# gizmo.net
KiCad netlist of a schematic drawn in EAGLE
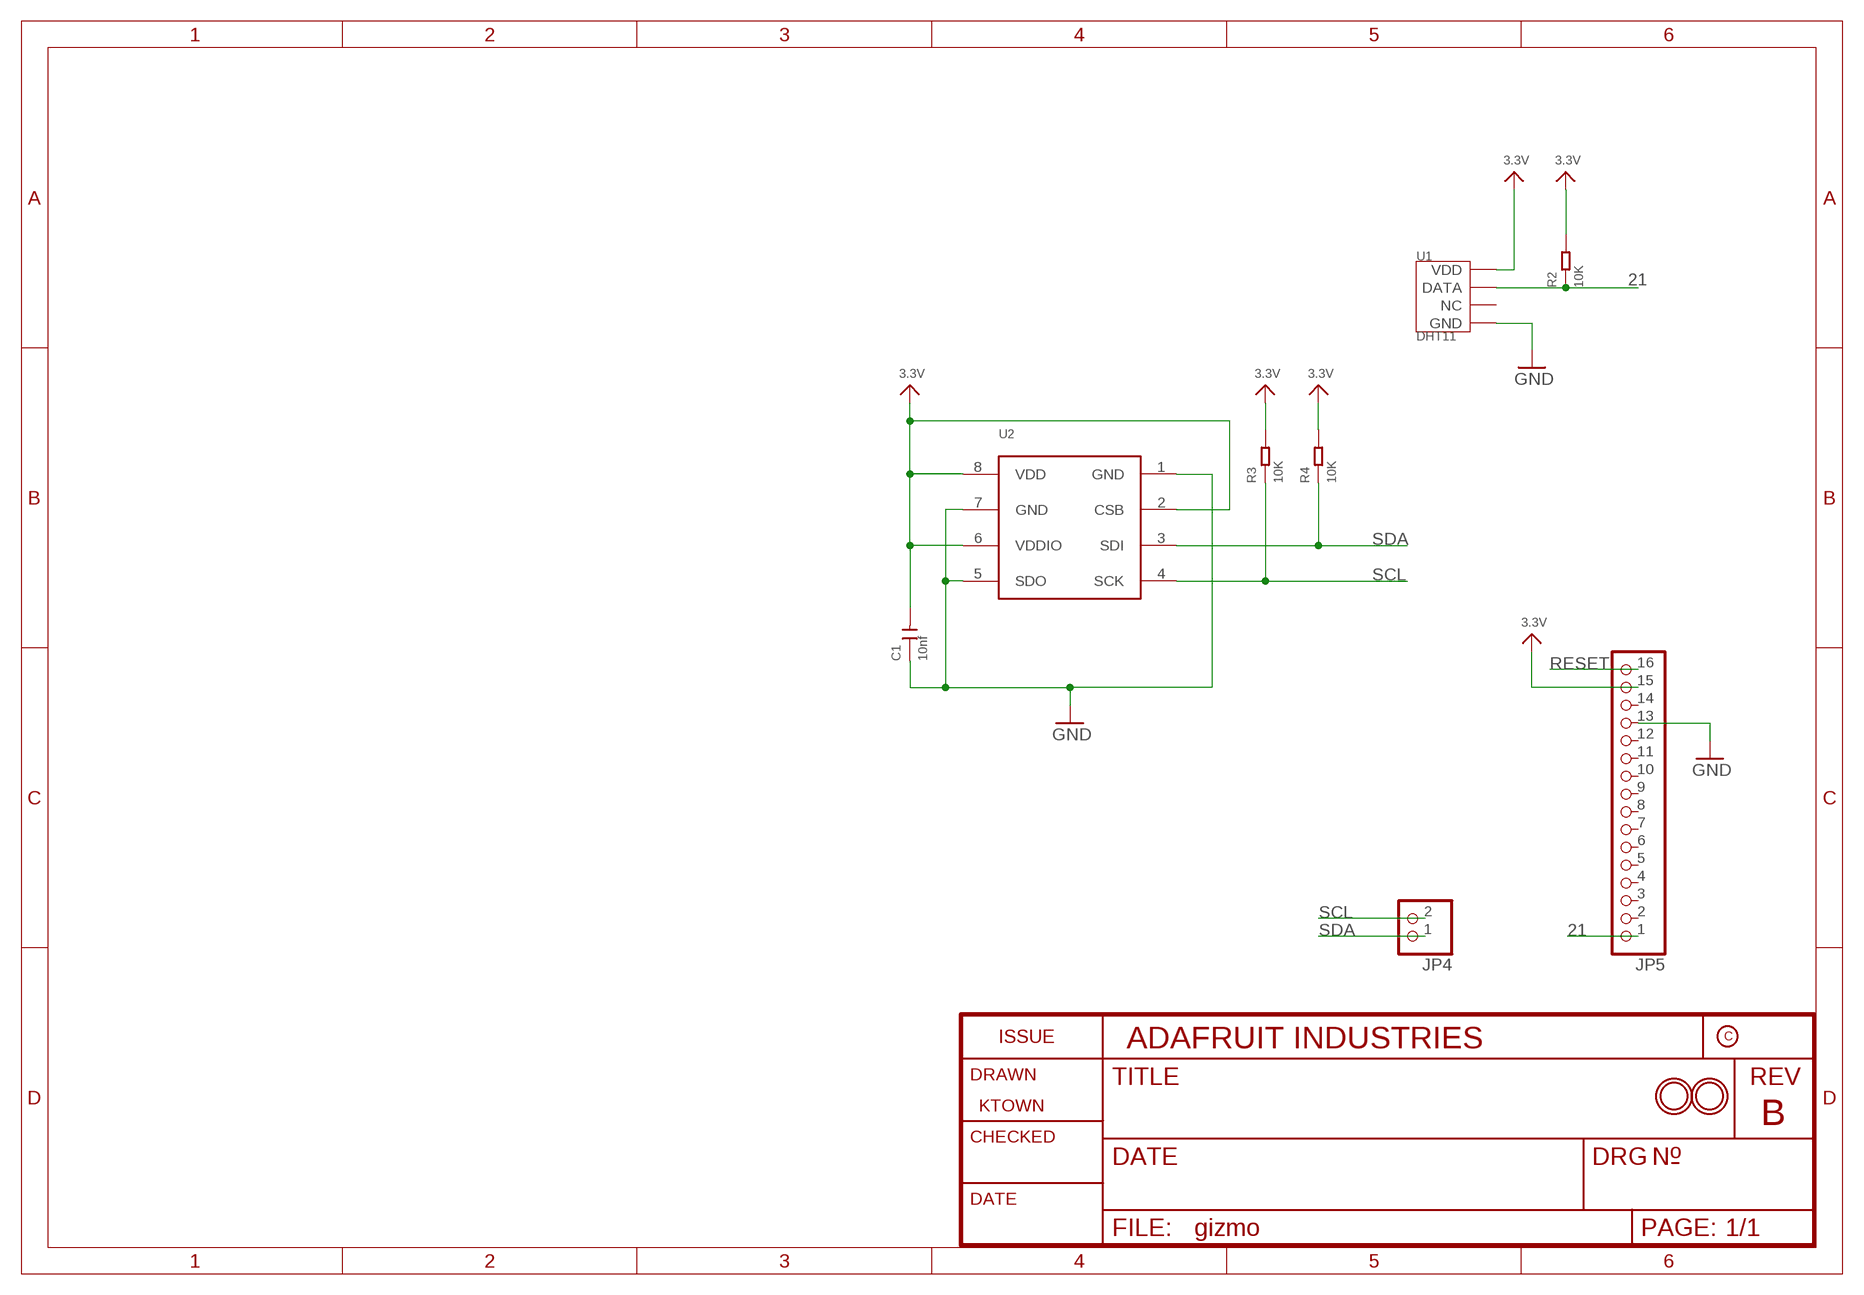
[diagram p0: schematic, sheet 1]

(export (version "E")
  (design (tool "Eeschema 10.0.6"))
  (components
    (comp (ref "C1")
      (value "10nf")
      (footprint "eagle-import:C0805")
      (fields (field (name "MPN") "CC0805JRX7R9BB103"))
      (libsource (lib "eagle-import") (part "CERAMIC-10NF-50V-5%-X7R(0805)"))
    )
    (comp (ref "JP4")
      (value "PINHD-1X2")
      (footprint "eagle-import:1X02")
      (libsource (lib "eagle-import") (part "PINHD-1X2"))
    )
    (comp (ref "JP5")
      (value "PINHD-1X16")
      (footprint "eagle-import:1X16")
      (libsource (lib "eagle-import") (part "PINHD-1X16"))
    )
    (comp (ref "R2")
      (value "10K")
      (footprint "eagle-import:R0603")
      (fields (field (name "MPN") "RC0603FR-0710KL"))
      (libsource (lib "eagle-import") (part "SMD-RES-10K-1%-1/10W(0603)"))
    )
    (comp (ref "R3")
      (value "10K")
      (footprint "eagle-import:R0603")
      (fields (field (name "MPN") "RC0603FR-0710KL"))
      (libsource (lib "eagle-import") (part "SMD-RES-10K-1%-1/10W(0603)"))
    )
    (comp (ref "R4")
      (value "10K")
      (footprint "eagle-import:R0603")
      (fields (field (name "MPN") "RC0603FR-0710KL"))
      (libsource (lib "eagle-import") (part "SMD-RES-10K-1%-1/10W(0603)"))
    )
    (comp (ref "U$31")
      (value "MOUNTINGHOLE2.5")
      (footprint "eagle-import:MOUNTINGHOLE_2.5_PLATED")
      (libsource (lib "eagle-import") (part "MOUNTINGHOLE2.5"))
    )
    (comp (ref "U$32")
      (value "MOUNTINGHOLE2.5")
      (footprint "eagle-import:MOUNTINGHOLE_2.5_PLATED")
      (libsource (lib "eagle-import") (part "MOUNTINGHOLE2.5"))
    )
    (comp (ref "U1")
      (value "DHT11")
      (footprint "eagle-import:SNR4-2.54-15.5X12.0X5.5MM")
      (libsource (lib "eagle-import") (part "TEM-HUM-DHT11(4P-15.5X12.0MM)"))
    )
    (comp (ref "U2")
      (value "BMP280")
      (footprint "eagle-import:BMP280")
      (libsource (lib "eagle-import") (part "BMP280"))
    )
  )
  (nets
    (net (code "1") (name "/21") (class "Default")
      (node (ref "JP5") (pin "1") (pinfunction "1_1") (pintype "passive"))
      (node (ref "R2") (pin "1") (pinfunction "1_1") (pintype "passive"))
      (node (ref "U1") (pin "2") (pinfunction "DATA_2") (pintype "bidirectional"))
    )
    (net (code "2") (name "/SCL") (class "Default")
      (node (ref "JP4") (pin "2") (pinfunction "2_2") (pintype "passive"))
      (node (ref "R3") (pin "1") (pinfunction "1_1") (pintype "passive"))
      (node (ref "U2") (pin "4") (pinfunction "SCK_4") (pintype "bidirectional"))
    )
    (net (code "3") (name "/SDA") (class "Default")
      (node (ref "JP4") (pin "1") (pinfunction "1_1") (pintype "passive"))
      (node (ref "R4") (pin "1") (pinfunction "1_1") (pintype "passive"))
      (node (ref "U2") (pin "3") (pinfunction "SDI_3") (pintype "bidirectional"))
    )
    (net (code "4") (name "3.3V") (class "Default")
      (node (ref "C1") (pin "2") (pinfunction "2_2") (pintype "passive"))
      (node (ref "JP5") (pin "15") (pinfunction "15_15") (pintype "passive"))
      (node (ref "R2") (pin "2") (pinfunction "2_2") (pintype "passive"))
      (node (ref "R3") (pin "2") (pinfunction "2_2") (pintype "passive"))
      (node (ref "R4") (pin "2") (pinfunction "2_2") (pintype "passive"))
      (node (ref "U1") (pin "1") (pinfunction "VDD_1") (pintype "power_in"))
      (node (ref "U2") (pin "2") (pinfunction "CSB_2") (pintype "bidirectional"))
      (node (ref "U2") (pin "6") (pinfunction "VDDIO_6") (pintype "bidirectional"))
      (node (ref "U2") (pin "8") (pinfunction "VDD_8") (pintype "bidirectional"))
    )
    (net (code "5") (name "GND") (class "Default")
      (node (ref "C1") (pin "1") (pinfunction "1_1") (pintype "passive"))
      (node (ref "JP5") (pin "13") (pinfunction "13_13") (pintype "passive"))
      (node (ref "U1") (pin "4") (pinfunction "GND_4") (pintype "power_in"))
      (node (ref "U2") (pin "1") (pinfunction "GND_1") (pintype "bidirectional"))
      (node (ref "U2") (pin "5") (pinfunction "SDO_5") (pintype "bidirectional"))
      (node (ref "U2") (pin "7") (pinfunction "GND_7") (pintype "bidirectional"))
    )
    (net (code "6") (name "unconnected-(JP5-Pad2)") (class "Default")
      (node (ref "JP5") (pin "2") (pinfunction "2_2") (pintype "passive"))
    )
    (net (code "7") (name "unconnected-(JP5-Pad3)") (class "Default")
      (node (ref "JP5") (pin "3") (pinfunction "3_3") (pintype "passive"))
    )
    (net (code "8") (name "unconnected-(JP5-Pad4)") (class "Default")
      (node (ref "JP5") (pin "4") (pinfunction "4_4") (pintype "passive"))
    )
    (net (code "9") (name "unconnected-(JP5-Pad5)") (class "Default")
      (node (ref "JP5") (pin "5") (pinfunction "5_5") (pintype "passive"))
    )
    (net (code "10") (name "unconnected-(JP5-Pad6)") (class "Default")
      (node (ref "JP5") (pin "6") (pinfunction "6_6") (pintype "passive"))
    )
    (net (code "11") (name "unconnected-(JP5-Pad7)") (class "Default")
      (node (ref "JP5") (pin "7") (pinfunction "7_7") (pintype "passive"))
    )
    (net (code "12") (name "unconnected-(JP5-Pad8)") (class "Default")
      (node (ref "JP5") (pin "8") (pinfunction "8_8") (pintype "passive"))
    )
    (net (code "13") (name "unconnected-(JP5-Pad9)") (class "Default")
      (node (ref "JP5") (pin "9") (pinfunction "9_9") (pintype "passive"))
    )
    (net (code "14") (name "unconnected-(JP5-Pad10)") (class "Default")
      (node (ref "JP5") (pin "10") (pinfunction "10_10") (pintype "passive"))
    )
    (net (code "15") (name "unconnected-(JP5-Pad11)") (class "Default")
      (node (ref "JP5") (pin "11") (pinfunction "11_11") (pintype "passive"))
    )
    (net (code "16") (name "unconnected-(JP5-Pad12)") (class "Default")
      (node (ref "JP5") (pin "12") (pinfunction "12_12") (pintype "passive"))
    )
    (net (code "17") (name "unconnected-(JP5-Pad14)") (class "Default")
      (node (ref "JP5") (pin "14") (pinfunction "14_14") (pintype "passive"))
    )
    (net (code "18") (name "unconnected-(JP5-Pad16)") (class "Default")
      (node (ref "JP5") (pin "16") (pinfunction "16_16") (pintype "passive"))
    )
    (net (code "19") (name "unconnected-(U1-NC-Pad3)") (class "Default")
      (node (ref "U1") (pin "3") (pinfunction "NC_3") (pintype "no_connect"))
    )
  )
)
